# 3EWL1-200001_05.net
KiCad netlist of a schematic drawn in Altium Designer
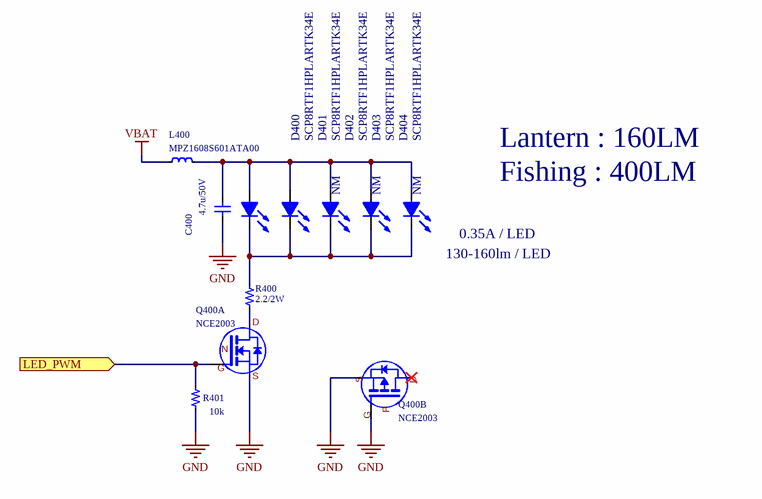
[diagram p0: 3EWL1-200001_05.SchDoc]

(export (version "E")
  (design (tool "Eeschema 10.0.6"))
  (components
    (comp (ref "C400")
      (value "4.7u/50V")
      (footprint "SC2-3.20X1.60A")
      (description "4.7u/50V, X7R, 3216Size")
      (fields
        (field (name "MANUFACTURER") "Murata")
        (field (name "MANUFACTURER PART NUMBER") "GRM31CR71H475KA12L")
      )
      (libsource (lib "I_Lib_cronos_NewLayer") (part "C"))
    )
    (comp (ref "D400")
      (value "SCP8RTF1HPLARTK34E")
      (footprint "SCP8RTF1HPLARTK34E")
      (description "2.75-3.4V, 315-363lm/A, 1919Size, SMT")
      (fields (field (name "MANUFACTURER") "SAMSUNG"))
      (libsource (lib "I_Lib_cronos_NewLayer") (part "Diode_LED"))
    )
    (comp (ref "D401")
      (value "SCP8RTF1HPLARTK34E")
      (footprint "SCP8RTF1HPLARTK34E")
      (description "2.75-3.4V, 315-363lm/A, 1919Size, SMT")
      (fields (field (name "MANUFACTURER") "SAMSUNG"))
      (libsource (lib "I_Lib_cronos_NewLayer") (part "Diode_LED"))
    )
    (comp (ref "D402")
      (value "SCP8RTF1HPLARTK34E")
      (footprint "SCP8RTF1HPLARTK34E")
      (description "2.75-3.4V, 315-363lm/A, 1919Size, SMT")
      (fields (field (name "MANUFACTURER") "SAMSUNG") (field (name "MOUNTING") "NM"))
      (libsource (lib "I_Lib_cronos_NewLayer") (part "Diode_LED"))
    )
    (comp (ref "D403")
      (value "SCP8RTF1HPLARTK34E")
      (footprint "SCP8RTF1HPLARTK34E")
      (description "2.75-3.4V, 315-363lm/A, 1919Size, SMT")
      (fields (field (name "MANUFACTURER") "SAMSUNG") (field (name "MOUNTING") "NM"))
      (libsource (lib "I_Lib_cronos_NewLayer") (part "Diode_LED"))
    )
    (comp (ref "D404")
      (value "SCP8RTF1HPLARTK34E")
      (footprint "SCP8RTF1HPLARTK34E")
      (description "2.75-3.4V, 315-363lm/A, 1919Size, SMT")
      (fields (field (name "MANUFACTURER") "SAMSUNG") (field (name "MOUNTING") "NM"))
      (libsource (lib "I_Lib_cronos_NewLayer") (part "Diode_LED"))
    )
    (comp (ref "L400")
      (value "MPZ1608S601ATA00")
      (footprint "SL2-1.60X0.80A")
      (description "600ohm/1.0A/150mohm")
      (fields
        (field (name "MANUFACTURER") "TDK")
        (field (name "MANUFACTURER PART NUMBER") "MPZ1608S601ATA00")
      )
      (libsource (lib "I_Lib_cronos_NewLayer") (part "L"))
    )
    (comp (ref "Q400")
      (value "NCE2003")
      (footprint "SOT23-6")
      (description "N(20V, 55mohm, Vgs(th)=1.2V ), P(-20V, 100mohm, Vgs(th)=-1V), SOT23-6")
      (fields (field (name "MANUFACTURER") "ncepower"))
      (libsource (lib "I_Lib_cronos_NewLayer") (part "NCE2003"))
    )
    (comp (ref "R400")
      (value "2.2/2W")
      (footprint "SR2-6.40x3.20A")
      (description "2.2, 2W, 6432Size")
      (fields
        (field (name "MANUFACTURER") "EverOhms")
        (field (name "MANUFACTURER PART NUMBER") "CRH2512F2R20E04Z")
      )
      (libsource (lib "I_Lib_cronos_NewLayer") (part "R"))
    )
    (comp (ref "R401")
      (value "10k")
      (footprint "SR2-1.00X0.50A")
      (fields
        (field (name "MANUFACTURER") "YAGEO")
        (field (name "MANUFACTURER PART NUMBER") "RC0402FR-0710KL")
      )
      (libsource (lib "I_Lib_cronos_NewLayer") (part "R"))
    )
  )
  (nets
    (net (code "1") (name "/LED_PWM") (class "Default")
      (node (ref "Q400") (pin "1") (pinfunction "N_G_1") (pintype "passive"))
      (node (ref "R401") (pin "1") (pinfunction "1_1") (pintype "passive"))
    )
    (net (code "2") (name "GND") (class "Default")
      (node (ref "C400") (pin "1") (pinfunction "1_1") (pintype "passive"))
      (node (ref "Q400") (pin "2") (pinfunction "P_S_2") (pintype "passive"))
      (node (ref "Q400") (pin "3") (pinfunction "P_G_3") (pintype "passive"))
      (node (ref "Q400") (pin "5") (pinfunction "N_S_5") (pintype "passive"))
      (node (ref "R401") (pin "2") (pinfunction "2_2") (pintype "passive"))
    )
    (net (code "3") (name "Net-(C400-Pad2)") (class "Default")
      (node (ref "C400") (pin "2") (pinfunction "2_2") (pintype "passive"))
      (node (ref "D400") (pin "A") (pinfunction "A_A") (pintype "passive"))
      (node (ref "D401") (pin "A") (pinfunction "A_A") (pintype "passive"))
      (node (ref "D402") (pin "A") (pinfunction "A_A") (pintype "passive"))
      (node (ref "D403") (pin "A") (pinfunction "A_A") (pintype "passive"))
      (node (ref "D404") (pin "A") (pinfunction "A_A") (pintype "passive"))
      (node (ref "L400") (pin "2") (pinfunction "2_2") (pintype "passive"))
    )
    (net (code "4") (name "Net-(D400-PadC)") (class "Default")
      (node (ref "D400") (pin "C") (pinfunction "C_C") (pintype "passive"))
      (node (ref "D401") (pin "C") (pinfunction "C_C") (pintype "passive"))
      (node (ref "D402") (pin "C") (pinfunction "C_C") (pintype "passive"))
      (node (ref "D403") (pin "C") (pinfunction "C_C") (pintype "passive"))
      (node (ref "D404") (pin "C") (pinfunction "C_C") (pintype "passive"))
      (node (ref "R400") (pin "1") (pinfunction "1_1") (pintype "passive"))
    )
    (net (code "5") (name "Net-(Q400A-N_D)") (class "Default")
      (node (ref "Q400") (pin "6") (pinfunction "N_D_6") (pintype "passive"))
      (node (ref "R400") (pin "2") (pinfunction "2_2") (pintype "passive"))
    )
    (net (code "6") (name "VBAT") (class "Default")
      (node (ref "L400") (pin "1") (pinfunction "1_1") (pintype "passive"))
    )
    (net (code "7") (name "unconnected-(Q400B-P_D-Pad4)") (class "Default")
      (node (ref "Q400") (pin "4") (pinfunction "P_D_4") (pintype "passive+no_connect"))
    )
  )
)
